# VIBRO.net
KiCad netlist of a schematic drawn in Altium Designer
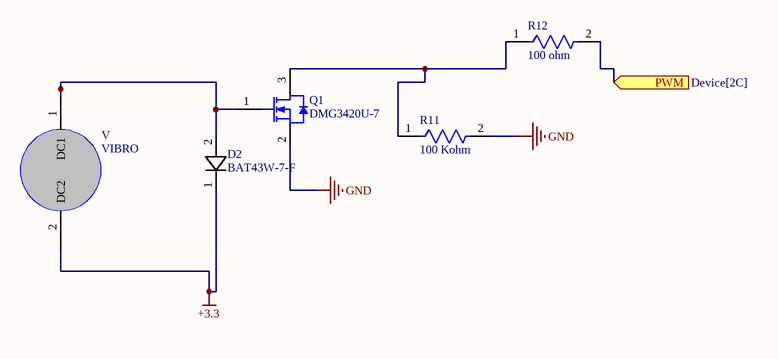
[diagram p0: VIBRO.SchDoc]

(export (version "E")
  (design (tool "Eeschema 10.0.6"))
  (components
    (comp (ref "D2")
      (value "BAT43W-7-F")
      (footprint "BAT43W-7-F")
      (libsource (lib "ReadyButNotListed") (part "BAT43W-7-F"))
    )
    (comp (ref "Q1")
      (value "DMG3420U-7")
      (footprint "DIOD-SOT23-3_B_V")
      (description "N-Channel Enhancement Mode MOSFET, 20 V, -55 to 150 degC, 3-Pin SOT23, RoHS, Tape and Reel")
      (fields (field (name "MANUFACTURER") "Diodes Inc"))
      (libsource (lib "Altium Content Vault") (part "NEMOS-GSD-3"))
    )
    (comp (ref "R11")
      (value "100 Kohm")
      (footprint "FP-RC1005-IPC_C")
      (description "Res Thick Film 0402 1.87kΩ 1% 0.063W ±100ppm/°C Molded SMD T/R")
      (fields (field (name "TOLERANCE") "1%"))
      (libsource (lib "Altium Content Vault") (part "1029c3af85768c4190bb7ad29bc67b5"))
    )
    (comp (ref "R12")
      (value "100 ohm")
      (footprint "FP-RC1005-IPC_C")
      (description "Res Thick Film 0402 1.87kΩ 1% 0.063W ±100ppm/°C Molded SMD T/R")
      (fields (field (name "TOLERANCE") "1%"))
      (libsource (lib "Altium Content Vault") (part "1029c3af85768c4190bb7ad29bc67b5"))
    )
    (comp (ref "V") (value "VIBRO") (footprint "VIBRO") (libsource (lib "Custom.") (part "VIBRO")))
  )
  (nets
    (net (code "1") (name "+3.3") (class "Default")
      (node (ref "D2") (pin "1") (pinfunction "1_1") (pintype "passive"))
      (node (ref "V") (pin "2") (pinfunction "DC2_2") (pintype "passive"))
    )
    (net (code "2") (name "/PWM") (class "Default")
      (node (ref "R12") (pin "2") (pinfunction "2_2") (pintype "passive"))
    )
    (net (code "3") (name "GND") (class "Default")
      (node (ref "Q1") (pin "2") (pinfunction "S_2") (pintype "passive"))
      (node (ref "R11") (pin "2") (pinfunction "2_2") (pintype "passive"))
    )
    (net (code "4") (name "Net-(Q1-D)") (class "Default")
      (node (ref "Q1") (pin "3") (pinfunction "D_3") (pintype "passive"))
      (node (ref "R11") (pin "1") (pinfunction "1_1") (pintype "passive"))
      (node (ref "R12") (pin "1") (pinfunction "1_1") (pintype "passive"))
    )
    (net (code "5") (name "Net-(Q1-G)") (class "Default")
      (node (ref "D2") (pin "2") (pinfunction "2_2") (pintype "passive"))
      (node (ref "Q1") (pin "1") (pinfunction "G_1") (pintype "passive"))
      (node (ref "V") (pin "1") (pinfunction "DC1_1") (pintype "passive"))
    )
  )
)
